# STM32F103CBU6.net
KiCad netlist of a schematic drawn in Altium Designer
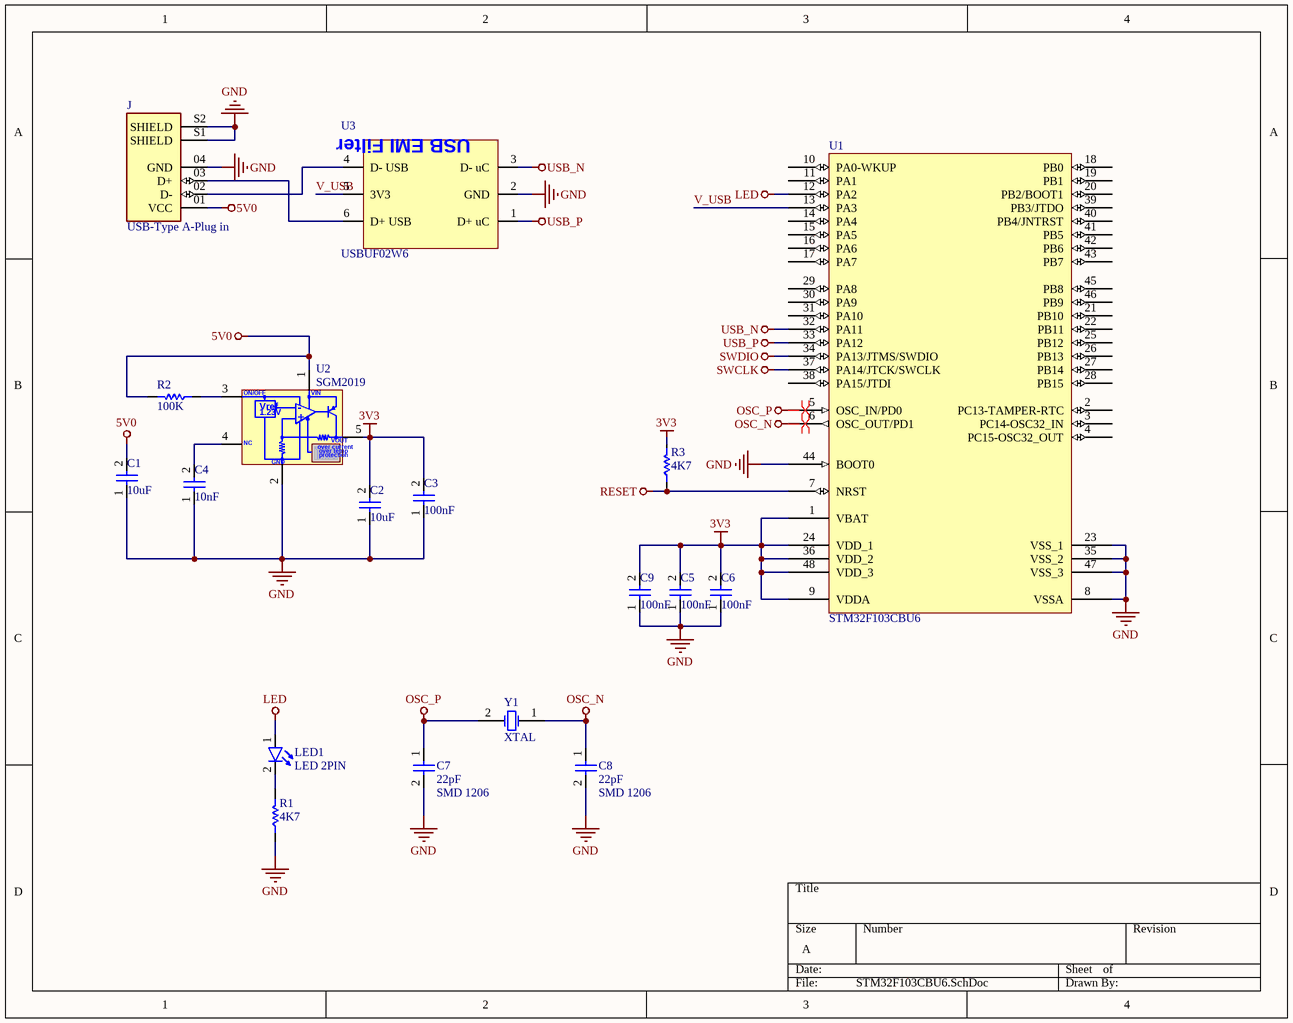
[diagram p0: STM32F103CBU6.SchDoc]

(export (version "E")
  (design (tool "Eeschema 10.0.6"))
  (components
    (comp (ref "C1") (value "10uF") (footprint "SMD 0805") (libsource (lib "3D LIB") (part "CAP NON")))
    (comp (ref "C2") (value "10uF") (footprint "SMD 0805") (libsource (lib "3D LIB") (part "CAP NON")))
    (comp (ref "C3") (value "100nF") (footprint "SMD 0805") (libsource (lib "3D LIB") (part "CAP NON")))
    (comp (ref "C4") (value "10nF") (footprint "SMD 0805") (libsource (lib "3D LIB") (part "CAP NON")))
    (comp (ref "C5") (value "100nF") (footprint "SMD 0805") (libsource (lib "3D LIB") (part "CAP NON")))
    (comp (ref "C6") (value "100nF") (footprint "SMD 0805") (libsource (lib "3D LIB") (part "CAP NON")))
    (comp (ref "C7")
      (value "22pF")
      (footprint "SMD 0805")
      (fields (field (name "ALTIUM_UNNAMED_8") "SMD 1206"))
      (libsource (lib "3D LIB") (part "CAP NON"))
    )
    (comp (ref "C8")
      (value "22pF")
      (footprint "SMD 0805")
      (fields (field (name "ALTIUM_UNNAMED_8") "SMD 1206"))
      (libsource (lib "3D LIB") (part "CAP NON"))
    )
    (comp (ref "C9") (value "100nF") (footprint "SMD 0805") (libsource (lib "3D LIB") (part "CAP NON")))
    (comp (ref "J")
      (value "USB-Type A-Plug in")
      (footprint "USB-TypeA-PlugIn")
      (description "USB-A (USB TYPE-A) USB 2.0 Plug Connector 4 Position Through Hole, Right Angle")
      (fields (field (name "MF") "Samtec") (field (name "MP") "USB-AM-S-F-B-TH"))
      (libsource (lib "SnapEDAsch") (part "USB-AM-S-X-X-TH"))
    )
    (comp (ref "LED1") (value "LED 2PIN") (footprint "LED 0805") (libsource (lib "3D LIB") (part "LED 2PIN")))
    (comp (ref "R1") (value "4K7") (footprint "0805_1/8W") (libsource (lib "3D LIB") (part "RESISTOR")))
    (comp (ref "R2") (value "100K") (footprint "0805_1/8W") (libsource (lib "3D LIB") (part "RESISTOR")))
    (comp (ref "R3") (value "4K7") (footprint "0805_1/8W") (libsource (lib "3D LIB") (part "RESISTOR")))
    (comp (ref "U1")
      (value "STM32F103CBU6")
      (footprint "QFN50P700X700X60-49N")
      (description "STM32 ARM-based 32-bit MCU with 128 Kbytes Flash, 48-pin LQFP, Industrial Temperature")
      (fields (field (name "PUBLISHER") "*"))
      (libsource (lib "3D LIB") (part "STM32F103CBT6"))
    )
    (comp (ref "U2") (value "SGM2019") (footprint "TSOT23") (libsource (lib "3D LIB") (part "L2980")))
    (comp (ref "U3")
      (value "USBUF02W6")
      (footprint "SOT323 6-Lead")
      (libsource (lib "3D LIB") (part "USBUF02W6"))
    )
    (comp (ref "Y1")
      (value "XTAL")
      (footprint "XTAL YIC 8.0000")
      (libsource (lib "3D_complite") (part "XTAL"))
    )
  )
  (nets
    (net (code "1") (name "/V_USB") (class "Default")
      (node (ref "U1") (pin "13") (pinfunction "PA3_13") (pintype "bidirectional"))
      (node (ref "U3") (pin "5") (pinfunction "3V3_5") (pintype "passive"))
    )
    (net (code "2") (name "3V3") (class "Default")
      (node (ref "C2") (pin "2") (pinfunction "2_2") (pintype "passive"))
      (node (ref "C3") (pin "2") (pinfunction "2_2") (pintype "passive"))
      (node (ref "C5") (pin "2") (pinfunction "2_2") (pintype "passive"))
      (node (ref "C6") (pin "2") (pinfunction "2_2") (pintype "passive"))
      (node (ref "C9") (pin "2") (pinfunction "2_2") (pintype "passive"))
      (node (ref "R3") (pin "2") (pinfunction "2_2") (pintype "passive"))
      (node (ref "U1") (pin "1") (pinfunction "VBAT_1") (pintype "power_in"))
      (node (ref "U1") (pin "24") (pinfunction "VDD_1_24") (pintype "power_in"))
      (node (ref "U1") (pin "36") (pinfunction "VDD_2_36") (pintype "power_in"))
      (node (ref "U1") (pin "48") (pinfunction "VDD_3_48") (pintype "power_in"))
      (node (ref "U1") (pin "9") (pinfunction "VDDA_9") (pintype "power_in"))
      (node (ref "U2") (pin "5") (pinfunction "VOUT_5") (pintype "passive"))
    )
    (net (code "3") (name "5V0") (class "Default")
      (node (ref "C1") (pin "2") (pinfunction "2_2") (pintype "passive"))
      (node (ref "J") (pin "01") (pinfunction "VCC_01") (pintype "power_in"))
      (node (ref "R2") (pin "2") (pinfunction "2_2") (pintype "passive"))
      (node (ref "U2") (pin "1") (pinfunction "VIN_1") (pintype "passive"))
    )
    (net (code "4") (name "GND") (class "Default")
      (node (ref "C1") (pin "1") (pinfunction "1_1") (pintype "passive"))
      (node (ref "C2") (pin "1") (pinfunction "1_1") (pintype "passive"))
      (node (ref "C3") (pin "1") (pinfunction "1_1") (pintype "passive"))
      (node (ref "C4") (pin "1") (pinfunction "1_1") (pintype "passive"))
      (node (ref "C5") (pin "1") (pinfunction "1_1") (pintype "passive"))
      (node (ref "C6") (pin "1") (pinfunction "1_1") (pintype "passive"))
      (node (ref "C7") (pin "2") (pinfunction "2_2") (pintype "passive"))
      (node (ref "C8") (pin "2") (pinfunction "2_2") (pintype "passive"))
      (node (ref "C9") (pin "1") (pinfunction "1_1") (pintype "passive"))
      (node (ref "J") (pin "04") (pinfunction "GND_04") (pintype "power_in"))
      (node (ref "J") (pin "S1") (pinfunction "SHIELD_S1") (pintype "passive"))
      (node (ref "J") (pin "S2") (pinfunction "SHIELD_S2") (pintype "passive"))
      (node (ref "R1") (pin "1") (pinfunction "1_1") (pintype "passive"))
      (node (ref "U1") (pin "23") (pinfunction "VSS_1_23") (pintype "power_in"))
      (node (ref "U1") (pin "35") (pinfunction "VSS_2_35") (pintype "power_in"))
      (node (ref "U1") (pin "44") (pinfunction "BOOT0_44") (pintype "input"))
      (node (ref "U1") (pin "47") (pinfunction "VSS_3_47") (pintype "power_in"))
      (node (ref "U1") (pin "8") (pinfunction "VSSA_8") (pintype "power_in"))
      (node (ref "U2") (pin "2") (pinfunction "GND_2") (pintype "passive"))
      (node (ref "U3") (pin "2") (pinfunction "GND_2") (pintype "passive"))
    )
    (net (code "5") (name "LED") (class "Default")
      (node (ref "LED1") (pin "1") (pinfunction "A_1") (pintype "passive"))
      (node (ref "U1") (pin "12") (pinfunction "PA2_12") (pintype "bidirectional"))
    )
    (net (code "6") (name "Net-(J-D+)") (class "Default")
      (node (ref "J") (pin "03") (pinfunction "D+_03") (pintype "bidirectional"))
      (node (ref "U3") (pin "6") (pinfunction "D+_USB_6") (pintype "passive"))
    )
    (net (code "7") (name "Net-(J-D-)") (class "Default")
      (node (ref "J") (pin "02") (pinfunction "D-_02") (pintype "bidirectional"))
      (node (ref "U3") (pin "4") (pinfunction "D-_USB_4") (pintype "passive"))
    )
    (net (code "8") (name "Net-(LED1-K)") (class "Default")
      (node (ref "LED1") (pin "2") (pinfunction "K_2") (pintype "passive"))
      (node (ref "R1") (pin "2") (pinfunction "2_2") (pintype "passive"))
    )
    (net (code "9") (name "Net-(U2-NC)") (class "Default")
      (node (ref "C4") (pin "2") (pinfunction "2_2") (pintype "passive"))
      (node (ref "U2") (pin "4") (pinfunction "NC_4") (pintype "passive"))
    )
    (net (code "10") (name "Net-(U2-ON{slash}OFF)") (class "Default")
      (node (ref "R2") (pin "1") (pinfunction "1_1") (pintype "passive"))
      (node (ref "U2") (pin "3") (pinfunction "ON/OFF_3") (pintype "passive"))
    )
    (net (code "11") (name "OSC_N") (class "Default")
      (node (ref "C8") (pin "1") (pinfunction "1_1") (pintype "passive"))
      (node (ref "U1") (pin "6") (pinfunction "OSC_OUT/PD1_6") (pintype "output"))
      (node (ref "Y1") (pin "1") (pinfunction "OSC1_1") (pintype "passive"))
    )
    (net (code "12") (name "OSC_P") (class "Default")
      (node (ref "C7") (pin "1") (pinfunction "1_1") (pintype "passive"))
      (node (ref "U1") (pin "5") (pinfunction "OSC_IN/PD0_5") (pintype "input"))
      (node (ref "Y1") (pin "2") (pinfunction "OSC2_2") (pintype "passive"))
    )
    (net (code "13") (name "RESET") (class "Default")
      (node (ref "R3") (pin "1") (pinfunction "1_1") (pintype "passive"))
      (node (ref "U1") (pin "7") (pinfunction "NRST_7") (pintype "bidirectional"))
    )
    (net (code "14") (name "SWCLK") (class "Default")
      (node (ref "U1") (pin "37") (pinfunction "PA14/JTCK/SWCLK_37") (pintype "bidirectional"))
    )
    (net (code "15") (name "SWDIO") (class "Default")
      (node (ref "U1") (pin "34") (pinfunction "PA13/JTMS/SWDIO_34") (pintype "bidirectional"))
    )
    (net (code "16") (name "USB_N") (class "Default")
      (node (ref "U1") (pin "32") (pinfunction "PA11_32") (pintype "bidirectional"))
      (node (ref "U3") (pin "3") (pinfunction "D-_uC_3") (pintype "passive"))
    )
    (net (code "17") (name "USB_P") (class "Default")
      (node (ref "U1") (pin "33") (pinfunction "PA12_33") (pintype "bidirectional"))
      (node (ref "U3") (pin "1") (pinfunction "D+_uC_1") (pintype "passive"))
    )
    (net (code "18") (name "unconnected-(U1-PA0-WKUP-Pad10)") (class "Default")
      (node (ref "U1") (pin "10") (pinfunction "PA0-WKUP_10") (pintype "bidirectional"))
    )
    (net (code "19") (name "unconnected-(U1-PA1-Pad11)") (class "Default")
      (node (ref "U1") (pin "11") (pinfunction "PA1_11") (pintype "bidirectional"))
    )
    (net (code "20") (name "unconnected-(U1-PA4-Pad14)") (class "Default")
      (node (ref "U1") (pin "14") (pinfunction "PA4_14") (pintype "bidirectional"))
    )
    (net (code "21") (name "unconnected-(U1-PA5-Pad15)") (class "Default")
      (node (ref "U1") (pin "15") (pinfunction "PA5_15") (pintype "bidirectional"))
    )
    (net (code "22") (name "unconnected-(U1-PA6-Pad16)") (class "Default")
      (node (ref "U1") (pin "16") (pinfunction "PA6_16") (pintype "bidirectional"))
    )
    (net (code "23") (name "unconnected-(U1-PA7-Pad17)") (class "Default")
      (node (ref "U1") (pin "17") (pinfunction "PA7_17") (pintype "bidirectional"))
    )
    (net (code "24") (name "unconnected-(U1-PA8-Pad29)") (class "Default")
      (node (ref "U1") (pin "29") (pinfunction "PA8_29") (pintype "bidirectional"))
    )
    (net (code "25") (name "unconnected-(U1-PA9-Pad30)") (class "Default")
      (node (ref "U1") (pin "30") (pinfunction "PA9_30") (pintype "bidirectional"))
    )
    (net (code "26") (name "unconnected-(U1-PA10-Pad31)") (class "Default")
      (node (ref "U1") (pin "31") (pinfunction "PA10_31") (pintype "bidirectional"))
    )
    (net (code "27") (name "unconnected-(U1-PA15{slash}JTDI-Pad38)") (class "Default")
      (node (ref "U1") (pin "38") (pinfunction "PA15/JTDI_38") (pintype "bidirectional"))
    )
    (net (code "28") (name "unconnected-(U1-PB0-Pad18)") (class "Default")
      (node (ref "U1") (pin "18") (pinfunction "PB0_18") (pintype "bidirectional"))
    )
    (net (code "29") (name "unconnected-(U1-PB1-Pad19)") (class "Default")
      (node (ref "U1") (pin "19") (pinfunction "PB1_19") (pintype "bidirectional"))
    )
    (net (code "30") (name "unconnected-(U1-PB2{slash}BOOT1-Pad20)") (class "Default")
      (node (ref "U1") (pin "20") (pinfunction "PB2/BOOT1_20") (pintype "bidirectional"))
    )
    (net (code "31") (name "unconnected-(U1-PB3{slash}JTDO-Pad39)") (class "Default")
      (node (ref "U1") (pin "39") (pinfunction "PB3/JTDO_39") (pintype "bidirectional"))
    )
    (net (code "32") (name "unconnected-(U1-PB4{slash}JNTRST-Pad40)") (class "Default")
      (node (ref "U1") (pin "40") (pinfunction "PB4/JNTRST_40") (pintype "bidirectional"))
    )
    (net (code "33") (name "unconnected-(U1-PB5-Pad41)") (class "Default")
      (node (ref "U1") (pin "41") (pinfunction "PB5_41") (pintype "bidirectional"))
    )
    (net (code "34") (name "unconnected-(U1-PB6-Pad42)") (class "Default")
      (node (ref "U1") (pin "42") (pinfunction "PB6_42") (pintype "bidirectional"))
    )
    (net (code "35") (name "unconnected-(U1-PB7-Pad43)") (class "Default")
      (node (ref "U1") (pin "43") (pinfunction "PB7_43") (pintype "bidirectional"))
    )
    (net (code "36") (name "unconnected-(U1-PB8-Pad45)") (class "Default")
      (node (ref "U1") (pin "45") (pinfunction "PB8_45") (pintype "bidirectional"))
    )
    (net (code "37") (name "unconnected-(U1-PB9-Pad46)") (class "Default")
      (node (ref "U1") (pin "46") (pinfunction "PB9_46") (pintype "bidirectional"))
    )
    (net (code "38") (name "unconnected-(U1-PB10-Pad21)") (class "Default")
      (node (ref "U1") (pin "21") (pinfunction "PB10_21") (pintype "bidirectional"))
    )
    (net (code "39") (name "unconnected-(U1-PB11-Pad22)") (class "Default")
      (node (ref "U1") (pin "22") (pinfunction "PB11_22") (pintype "bidirectional"))
    )
    (net (code "40") (name "unconnected-(U1-PB12-Pad25)") (class "Default")
      (node (ref "U1") (pin "25") (pinfunction "PB12_25") (pintype "bidirectional"))
    )
    (net (code "41") (name "unconnected-(U1-PB13-Pad26)") (class "Default")
      (node (ref "U1") (pin "26") (pinfunction "PB13_26") (pintype "bidirectional"))
    )
    (net (code "42") (name "unconnected-(U1-PB14-Pad27)") (class "Default")
      (node (ref "U1") (pin "27") (pinfunction "PB14_27") (pintype "bidirectional"))
    )
    (net (code "43") (name "unconnected-(U1-PB15-Pad28)") (class "Default")
      (node (ref "U1") (pin "28") (pinfunction "PB15_28") (pintype "bidirectional"))
    )
    (net (code "44") (name "unconnected-(U1-PC13-TAMPER-RTC-Pad2)") (class "Default")
      (node (ref "U1") (pin "2") (pinfunction "PC13-TAMPER-RTC_2") (pintype "bidirectional"))
    )
    (net (code "45") (name "unconnected-(U1-PC14-OSC32_IN-Pad3)") (class "Default")
      (node (ref "U1") (pin "3") (pinfunction "PC14-OSC32_IN_3") (pintype "bidirectional"))
    )
    (net (code "46") (name "unconnected-(U1-PC15-OSC32_OUT-Pad4)") (class "Default")
      (node (ref "U1") (pin "4") (pinfunction "PC15-OSC32_OUT_4") (pintype "bidirectional"))
    )
  )
)
